# Breakout_ICM-20948.net
KiCad netlist of a schematic drawn in EAGLE
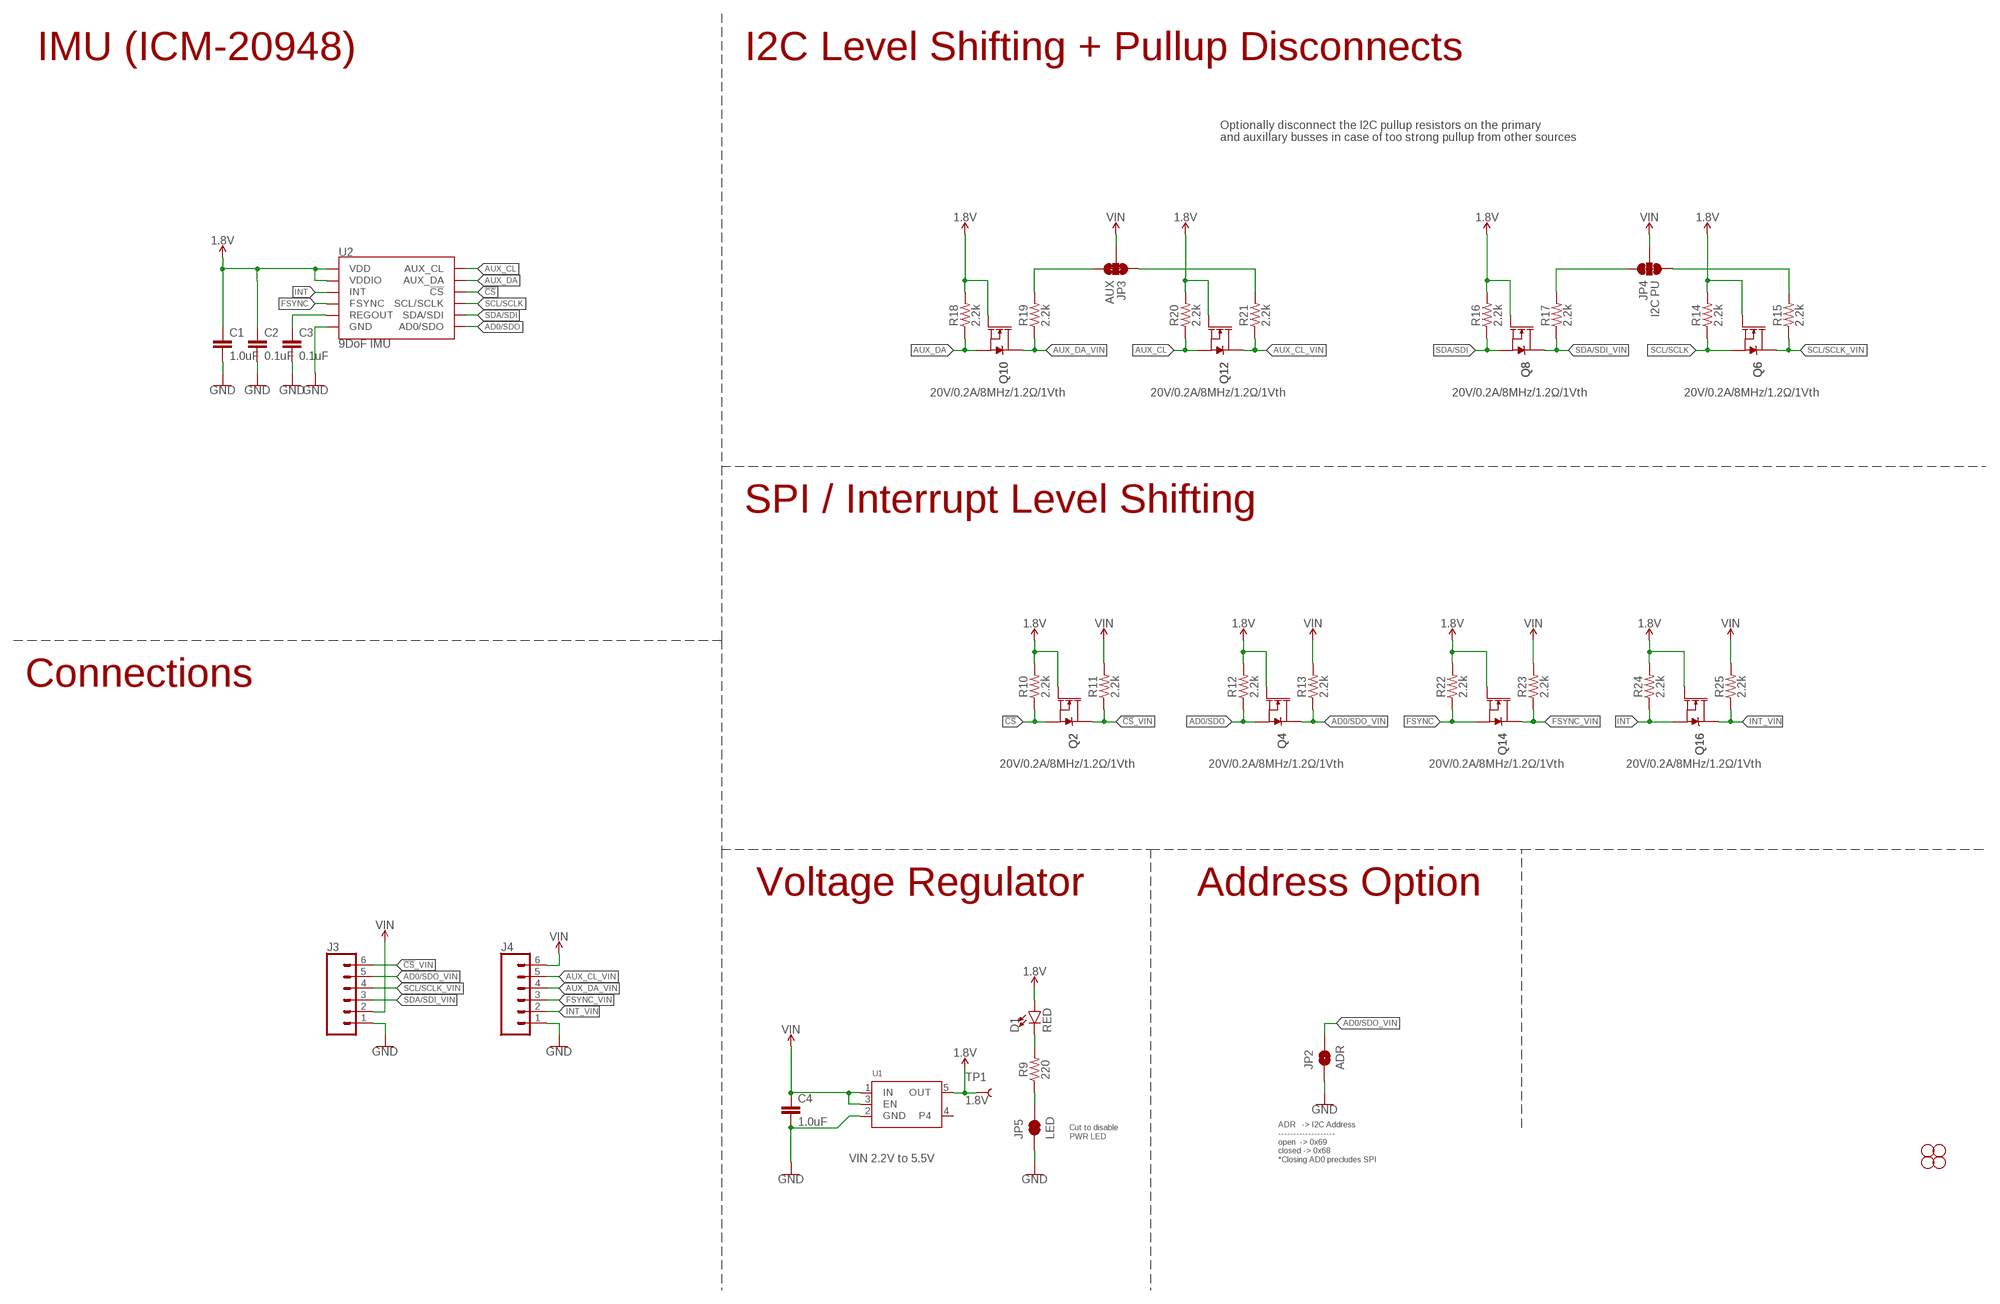
[diagram p0: schematic, sheet 1]

(export (version "E")
  (design (tool "Eeschema 10.0.6"))
  (components
    (comp (ref "C1")
      (value "1.0uF")
      (footprint "eagle-import:0603")
      (libsource (lib "eagle-import") (part "1.0UF-0603-16V-10%-X7R"))
    )
    (comp (ref "C2")
      (value "0.1uF")
      (footprint "eagle-import:0603")
      (libsource (lib "eagle-import") (part "0.1UF-0603-25V-5%"))
    )
    (comp (ref "C3")
      (value "0.1uF")
      (footprint "eagle-import:0603")
      (libsource (lib "eagle-import") (part "0.1UF-0603-25V-5%"))
    )
    (comp (ref "C4")
      (value "1.0uF")
      (footprint "eagle-import:0603")
      (libsource (lib "eagle-import") (part "1.0UF-0603-16V-10%-X7R"))
    )
    (comp (ref "D1")
      (value "RED")
      (footprint "eagle-import:LED-0603")
      (libsource (lib "eagle-import") (part "LED-RED0603"))
    )
    (comp (ref "H1")
      (value "STAND-OFF")
      (footprint "eagle-import:STAND-OFF")
      (libsource (lib "eagle-import") (part "STAND-OFF"))
    )
    (comp (ref "H2")
      (value "STAND-OFF")
      (footprint "eagle-import:STAND-OFF")
      (libsource (lib "eagle-import") (part "STAND-OFF"))
    )
    (comp (ref "H3")
      (value "STAND-OFF")
      (footprint "eagle-import:STAND-OFF")
      (libsource (lib "eagle-import") (part "STAND-OFF"))
    )
    (comp (ref "H4")
      (value "STAND-OFF")
      (footprint "eagle-import:STAND-OFF")
      (libsource (lib "eagle-import") (part "STAND-OFF"))
    )
    (comp (ref "J3")
      (value "CONN_06NO_SILK_NO_POP")
      (footprint "eagle-import:1X06_NO_SILK")
      (libsource (lib "eagle-import") (part "CONN_06NO_SILK_NO_POP"))
    )
    (comp (ref "J4")
      (value "CONN_06NO_SILK_NO_POP")
      (footprint "eagle-import:1X06_NO_SILK")
      (libsource (lib "eagle-import") (part "CONN_06NO_SILK_NO_POP"))
    )
    (comp (ref "JP2")
      (value "ADR")
      (footprint "eagle-import:SMT-JUMPER_2_NO_SILK")
      (libsource (lib "eagle-import") (part "JUMPER-SMT_2_NO_SILK"))
    )
    (comp (ref "JP3")
      (value "AUX")
      (footprint "eagle-import:SMT-JUMPER_3_2-NC_TRACE_SILK")
      (libsource (lib "eagle-import") (part "JUMPER-SMT_3_2-NC_TRACE_SILK"))
    )
    (comp (ref "JP4")
      (value "I2C PU")
      (footprint "eagle-import:SMT-JUMPER_3_2-NC_TRACE_SILK")
      (libsource (lib "eagle-import") (part "JUMPER-SMT_3_2-NC_TRACE_SILK"))
    )
    (comp (ref "JP5")
      (value "LED")
      (footprint "eagle-import:SMT-JUMPER_2_NC_TRACE_SILK")
      (libsource (lib "eagle-import") (part "JUMPER-SMT_2_NC_TRACE_SILK"))
    )
    (comp (ref "Q2")
      (value "20V/0.2A/8MHz/1.2Ω/1Vth")
      (footprint "eagle-import:SOT-416FL")
      (libsource (lib "eagle-import") (part "MOSFET-NCH-RE1C002UN"))
    )
    (comp (ref "Q4")
      (value "20V/0.2A/8MHz/1.2Ω/1Vth")
      (footprint "eagle-import:SOT-416FL")
      (libsource (lib "eagle-import") (part "MOSFET-NCH-RE1C002UN"))
    )
    (comp (ref "Q6")
      (value "20V/0.2A/8MHz/1.2Ω/1Vth")
      (footprint "eagle-import:SOT-416FL")
      (libsource (lib "eagle-import") (part "MOSFET-NCH-RE1C002UN"))
    )
    (comp (ref "Q8")
      (value "20V/0.2A/8MHz/1.2Ω/1Vth")
      (footprint "eagle-import:SOT-416FL")
      (libsource (lib "eagle-import") (part "MOSFET-NCH-RE1C002UN"))
    )
    (comp (ref "Q10")
      (value "20V/0.2A/8MHz/1.2Ω/1Vth")
      (footprint "eagle-import:SOT-416FL")
      (libsource (lib "eagle-import") (part "MOSFET-NCH-RE1C002UN"))
    )
    (comp (ref "Q12")
      (value "20V/0.2A/8MHz/1.2Ω/1Vth")
      (footprint "eagle-import:SOT-416FL")
      (libsource (lib "eagle-import") (part "MOSFET-NCH-RE1C002UN"))
    )
    (comp (ref "Q14")
      (value "20V/0.2A/8MHz/1.2Ω/1Vth")
      (footprint "eagle-import:SOT-416FL")
      (libsource (lib "eagle-import") (part "MOSFET-NCH-RE1C002UN"))
    )
    (comp (ref "Q16")
      (value "20V/0.2A/8MHz/1.2Ω/1Vth")
      (footprint "eagle-import:SOT-416FL")
      (libsource (lib "eagle-import") (part "MOSFET-NCH-RE1C002UN"))
    )
    (comp (ref "R9")
      (value "220")
      (footprint "eagle-import:0603")
      (libsource (lib "eagle-import") (part "220OHM-0603-1/10W-1%"))
    )
    (comp (ref "R10")
      (value "2.2k")
      (footprint "eagle-import:0402-TIGHT")
      (libsource (lib "eagle-import") (part "2.2KOHM-0402T-1/16W-1%"))
    )
    (comp (ref "R11")
      (value "2.2k")
      (footprint "eagle-import:0402-TIGHT")
      (libsource (lib "eagle-import") (part "2.2KOHM-0402T-1/16W-1%"))
    )
    (comp (ref "R12")
      (value "2.2k")
      (footprint "eagle-import:0402-TIGHT")
      (libsource (lib "eagle-import") (part "2.2KOHM-0402T-1/16W-1%"))
    )
    (comp (ref "R13")
      (value "2.2k")
      (footprint "eagle-import:0402-TIGHT")
      (libsource (lib "eagle-import") (part "2.2KOHM-0402T-1/16W-1%"))
    )
    (comp (ref "R14")
      (value "2.2k")
      (footprint "eagle-import:0402-TIGHT")
      (libsource (lib "eagle-import") (part "2.2KOHM-0402T-1/16W-1%"))
    )
    (comp (ref "R15")
      (value "2.2k")
      (footprint "eagle-import:0402-TIGHT")
      (libsource (lib "eagle-import") (part "2.2KOHM-0402T-1/16W-1%"))
    )
    (comp (ref "R16")
      (value "2.2k")
      (footprint "eagle-import:0402-TIGHT")
      (libsource (lib "eagle-import") (part "2.2KOHM-0402T-1/16W-1%"))
    )
    (comp (ref "R17")
      (value "2.2k")
      (footprint "eagle-import:0402-TIGHT")
      (libsource (lib "eagle-import") (part "2.2KOHM-0402T-1/16W-1%"))
    )
    (comp (ref "R18")
      (value "2.2k")
      (footprint "eagle-import:0402-TIGHT")
      (libsource (lib "eagle-import") (part "2.2KOHM-0402T-1/16W-1%"))
    )
    (comp (ref "R19")
      (value "2.2k")
      (footprint "eagle-import:0402-TIGHT")
      (libsource (lib "eagle-import") (part "2.2KOHM-0402T-1/16W-1%"))
    )
    (comp (ref "R20")
      (value "2.2k")
      (footprint "eagle-import:0402-TIGHT")
      (libsource (lib "eagle-import") (part "2.2KOHM-0402T-1/16W-1%"))
    )
    (comp (ref "R21")
      (value "2.2k")
      (footprint "eagle-import:0402-TIGHT")
      (libsource (lib "eagle-import") (part "2.2KOHM-0402T-1/16W-1%"))
    )
    (comp (ref "R22")
      (value "2.2k")
      (footprint "eagle-import:0402-TIGHT")
      (libsource (lib "eagle-import") (part "2.2KOHM-0402T-1/16W-1%"))
    )
    (comp (ref "R23")
      (value "2.2k")
      (footprint "eagle-import:0402-TIGHT")
      (libsource (lib "eagle-import") (part "2.2KOHM-0402T-1/16W-1%"))
    )
    (comp (ref "R24")
      (value "2.2k")
      (footprint "eagle-import:0402-TIGHT")
      (libsource (lib "eagle-import") (part "2.2KOHM-0402T-1/16W-1%"))
    )
    (comp (ref "R25")
      (value "2.2k")
      (footprint "eagle-import:0402-TIGHT")
      (libsource (lib "eagle-import") (part "2.2KOHM-0402T-1/16W-1%"))
    )
    (comp (ref "TP1")
      (value "1.8V")
      (footprint "eagle-import:PAD.03X.03")
      (libsource (lib "eagle-import") (part "TEST-POINT3"))
    )
    (comp (ref "U1")
      (value "MICROBUILDER_VREG_SOT23-5")
      (footprint "eagle-import:MICROBUILDER_SOT23-5")
      (libsource (lib "eagle-import") (part "MICROBUILDER_VREG_SOT23-5"))
    )
    (comp (ref "U2")
      (value "9DoF IMU")
      (footprint "eagle-import:QFN24-3X3")
      (libsource (lib "eagle-import") (part "ICM-20948"))
    )
  )
  (nets
    (net (code "1") (name "/~{CS}") (class "Default")
      (node (ref "Q2") (pin "2") (pinfunction "S_2") (pintype "bidirectional"))
      (node (ref "R10") (pin "1") (pinfunction "1_1") (pintype "passive"))
      (node (ref "U2") (pin "22") (pinfunction "~{CS}_22") (pintype "bidirectional"))
    )
    (net (code "2") (name "/~{CS}_VIN") (class "Default")
      (node (ref "J3") (pin "6") (pinfunction "6_6") (pintype "passive"))
      (node (ref "Q2") (pin "3") (pinfunction "D_3") (pintype "bidirectional"))
      (node (ref "R11") (pin "1") (pinfunction "1_1") (pintype "passive"))
    )
    (net (code "3") (name "1.8V") (class "Default")
      (node (ref "C1") (pin "1") (pinfunction "1_1") (pintype "passive"))
      (node (ref "C2") (pin "1") (pinfunction "1_1") (pintype "passive"))
      (node (ref "D1") (pin "A") (pinfunction "A_A") (pintype "passive"))
      (node (ref "Q10") (pin "1") (pinfunction "G_1") (pintype "bidirectional"))
      (node (ref "Q12") (pin "1") (pinfunction "G_1") (pintype "bidirectional"))
      (node (ref "Q14") (pin "1") (pinfunction "G_1") (pintype "bidirectional"))
      (node (ref "Q16") (pin "1") (pinfunction "G_1") (pintype "bidirectional"))
      (node (ref "Q2") (pin "1") (pinfunction "G_1") (pintype "bidirectional"))
      (node (ref "Q4") (pin "1") (pinfunction "G_1") (pintype "bidirectional"))
      (node (ref "Q6") (pin "1") (pinfunction "G_1") (pintype "bidirectional"))
      (node (ref "Q8") (pin "1") (pinfunction "G_1") (pintype "bidirectional"))
      (node (ref "R10") (pin "2") (pinfunction "2_2") (pintype "passive"))
      (node (ref "R12") (pin "2") (pinfunction "2_2") (pintype "passive"))
      (node (ref "R14") (pin "2") (pinfunction "2_2") (pintype "passive"))
      (node (ref "R16") (pin "2") (pinfunction "2_2") (pintype "passive"))
      (node (ref "R18") (pin "2") (pinfunction "2_2") (pintype "passive"))
      (node (ref "R20") (pin "2") (pinfunction "2_2") (pintype "passive"))
      (node (ref "R22") (pin "2") (pinfunction "2_2") (pintype "passive"))
      (node (ref "R24") (pin "2") (pinfunction "2_2") (pintype "passive"))
      (node (ref "TP1") (pin "P$1") (pinfunction "1_P$1") (pintype "bidirectional"))
      (node (ref "U1") (pin "5") (pinfunction "OUT_5") (pintype "power_in"))
      (node (ref "U2") (pin "13") (pinfunction "VDD_13") (pintype "bidirectional"))
      (node (ref "U2") (pin "8") (pinfunction "VDDIO_8") (pintype "bidirectional"))
    )
    (net (code "4") (name "AD0{slash}SDO") (class "Default")
      (node (ref "Q4") (pin "2") (pinfunction "S_2") (pintype "bidirectional"))
      (node (ref "R12") (pin "1") (pinfunction "1_1") (pintype "passive"))
      (node (ref "U2") (pin "9") (pinfunction "AD0/SDO_9") (pintype "bidirectional"))
    )
    (net (code "5") (name "AD0{slash}SDO_VIN") (class "Default")
      (node (ref "J3") (pin "5") (pinfunction "5_5") (pintype "passive"))
      (node (ref "JP2") (pin "2") (pinfunction "2_2") (pintype "passive"))
      (node (ref "Q4") (pin "3") (pinfunction "D_3") (pintype "bidirectional"))
      (node (ref "R13") (pin "1") (pinfunction "1_1") (pintype "passive"))
    )
    (net (code "6") (name "AUX_CL") (class "Default")
      (node (ref "Q12") (pin "2") (pinfunction "S_2") (pintype "bidirectional"))
      (node (ref "R20") (pin "1") (pinfunction "1_1") (pintype "passive"))
      (node (ref "U2") (pin "7") (pinfunction "AUX_CL_7") (pintype "bidirectional"))
    )
    (net (code "7") (name "AUX_CL_VIN") (class "Default")
      (node (ref "J4") (pin "5") (pinfunction "5_5") (pintype "passive"))
      (node (ref "Q12") (pin "3") (pinfunction "D_3") (pintype "bidirectional"))
      (node (ref "R21") (pin "1") (pinfunction "1_1") (pintype "passive"))
    )
    (net (code "8") (name "AUX_DA") (class "Default")
      (node (ref "Q10") (pin "2") (pinfunction "S_2") (pintype "bidirectional"))
      (node (ref "R18") (pin "1") (pinfunction "1_1") (pintype "passive"))
      (node (ref "U2") (pin "21") (pinfunction "AUX_DA_21") (pintype "bidirectional"))
    )
    (net (code "9") (name "AUX_DA_VIN") (class "Default")
      (node (ref "J4") (pin "4") (pinfunction "4_4") (pintype "passive"))
      (node (ref "Q10") (pin "3") (pinfunction "D_3") (pintype "bidirectional"))
      (node (ref "R19") (pin "1") (pinfunction "1_1") (pintype "passive"))
    )
    (net (code "10") (name "FSYNC") (class "Default")
      (node (ref "Q14") (pin "2") (pinfunction "S_2") (pintype "bidirectional"))
      (node (ref "R22") (pin "1") (pinfunction "1_1") (pintype "passive"))
      (node (ref "U2") (pin "11") (pinfunction "FSYNC_11") (pintype "bidirectional"))
    )
    (net (code "11") (name "FSYNC_VIN") (class "Default")
      (node (ref "J4") (pin "3") (pinfunction "3_3") (pintype "passive"))
      (node (ref "Q14") (pin "3") (pinfunction "D_3") (pintype "bidirectional"))
      (node (ref "R23") (pin "1") (pinfunction "1_1") (pintype "passive"))
    )
    (net (code "12") (name "GND") (class "Default")
      (node (ref "C1") (pin "2") (pinfunction "2_2") (pintype "passive"))
      (node (ref "C2") (pin "2") (pinfunction "2_2") (pintype "passive"))
      (node (ref "C3") (pin "2") (pinfunction "2_2") (pintype "passive"))
      (node (ref "C4") (pin "2") (pinfunction "2_2") (pintype "passive"))
      (node (ref "J3") (pin "1") (pinfunction "1_1") (pintype "passive"))
      (node (ref "J4") (pin "1") (pinfunction "1_1") (pintype "passive"))
      (node (ref "JP2") (pin "1") (pinfunction "1_1") (pintype "passive"))
      (node (ref "JP5") (pin "1") (pinfunction "1_1") (pintype "passive"))
      (node (ref "U1") (pin "2") (pinfunction "GND_2") (pintype "power_in"))
      (node (ref "U2") (pin "18") (pinfunction "GND_18") (pintype "bidirectional"))
      (node (ref "U2") (pin "20") (pinfunction "GND_20") (pintype "bidirectional"))
    )
    (net (code "13") (name "INT") (class "Default")
      (node (ref "Q16") (pin "2") (pinfunction "S_2") (pintype "bidirectional"))
      (node (ref "R24") (pin "1") (pinfunction "1_1") (pintype "passive"))
      (node (ref "U2") (pin "12") (pinfunction "INT_12") (pintype "bidirectional"))
    )
    (net (code "14") (name "INT_VIN") (class "Default")
      (node (ref "J4") (pin "2") (pinfunction "2_2") (pintype "passive"))
      (node (ref "Q16") (pin "3") (pinfunction "D_3") (pintype "bidirectional"))
      (node (ref "R25") (pin "1") (pinfunction "1_1") (pintype "passive"))
    )
    (net (code "15") (name "Net-(D1-PadC)") (class "Default")
      (node (ref "D1") (pin "C") (pinfunction "C_C") (pintype "passive"))
      (node (ref "R9") (pin "2") (pinfunction "2_2") (pintype "passive"))
    )
    (net (code "16") (name "Net-(JP3-Pad1)") (class "Default")
      (node (ref "JP3") (pin "1") (pinfunction "1_1") (pintype "passive"))
      (node (ref "R21") (pin "2") (pinfunction "2_2") (pintype "passive"))
    )
    (net (code "17") (name "Net-(JP3-Pad3)") (class "Default")
      (node (ref "JP3") (pin "3") (pinfunction "3_3") (pintype "passive"))
      (node (ref "R19") (pin "2") (pinfunction "2_2") (pintype "passive"))
    )
    (net (code "18") (name "Net-(JP4-Pad1)") (class "Default")
      (node (ref "JP4") (pin "1") (pinfunction "1_1") (pintype "passive"))
      (node (ref "R17") (pin "2") (pinfunction "2_2") (pintype "passive"))
    )
    (net (code "19") (name "Net-(JP4-Pad3)") (class "Default")
      (node (ref "JP4") (pin "3") (pinfunction "3_3") (pintype "passive"))
      (node (ref "R15") (pin "2") (pinfunction "2_2") (pintype "passive"))
    )
    (net (code "20") (name "Net-(JP5-Pad2)") (class "Default")
      (node (ref "JP5") (pin "2") (pinfunction "2_2") (pintype "passive"))
      (node (ref "R9") (pin "1") (pinfunction "1_1") (pintype "passive"))
    )
    (net (code "21") (name "Net-(U2-REGOUT)") (class "Default")
      (node (ref "C3") (pin "1") (pinfunction "1_1") (pintype "passive"))
      (node (ref "U2") (pin "10") (pinfunction "REGOUT_10") (pintype "bidirectional"))
    )
    (net (code "22") (name "SCL{slash}SCLK") (class "Default")
      (node (ref "Q6") (pin "2") (pinfunction "S_2") (pintype "bidirectional"))
      (node (ref "R14") (pin "1") (pinfunction "1_1") (pintype "passive"))
      (node (ref "U2") (pin "23") (pinfunction "SCL/SCLK_23") (pintype "bidirectional"))
    )
    (net (code "23") (name "SCL{slash}SCLK_VIN") (class "Default")
      (node (ref "J3") (pin "4") (pinfunction "4_4") (pintype "passive"))
      (node (ref "Q6") (pin "3") (pinfunction "D_3") (pintype "bidirectional"))
      (node (ref "R15") (pin "1") (pinfunction "1_1") (pintype "passive"))
    )
    (net (code "24") (name "SDA{slash}SDI") (class "Default")
      (node (ref "Q8") (pin "2") (pinfunction "S_2") (pintype "bidirectional"))
      (node (ref "R16") (pin "1") (pinfunction "1_1") (pintype "passive"))
      (node (ref "U2") (pin "24") (pinfunction "SDA/SDI_24") (pintype "bidirectional"))
    )
    (net (code "25") (name "SDA{slash}SDI_VIN") (class "Default")
      (node (ref "J3") (pin "3") (pinfunction "3_3") (pintype "passive"))
      (node (ref "Q8") (pin "3") (pinfunction "D_3") (pintype "bidirectional"))
      (node (ref "R17") (pin "1") (pinfunction "1_1") (pintype "passive"))
    )
    (net (code "26") (name "VIN") (class "Default")
      (node (ref "C4") (pin "1") (pinfunction "1_1") (pintype "passive"))
      (node (ref "J3") (pin "2") (pinfunction "2_2") (pintype "passive"))
      (node (ref "J4") (pin "6") (pinfunction "6_6") (pintype "passive"))
      (node (ref "JP3") (pin "2") (pinfunction "2_2") (pintype "passive"))
      (node (ref "JP4") (pin "2") (pinfunction "2_2") (pintype "passive"))
      (node (ref "R11") (pin "2") (pinfunction "2_2") (pintype "passive"))
      (node (ref "R13") (pin "2") (pinfunction "2_2") (pintype "passive"))
      (node (ref "R23") (pin "2") (pinfunction "2_2") (pintype "passive"))
      (node (ref "R25") (pin "2") (pinfunction "2_2") (pintype "passive"))
      (node (ref "U1") (pin "1") (pinfunction "IN_1") (pintype "power_in"))
      (node (ref "U1") (pin "3") (pinfunction "EN_3") (pintype "input"))
    )
    (net (code "27") (name "unconnected-(U1-P4-Pad4)") (class "Default")
      (node (ref "U1") (pin "4") (pinfunction "P4_4") (pintype "bidirectional"))
    )
  )
)
